# eurorack-passive-warp.net
KiCad netlist of a schematic drawn in EAGLE
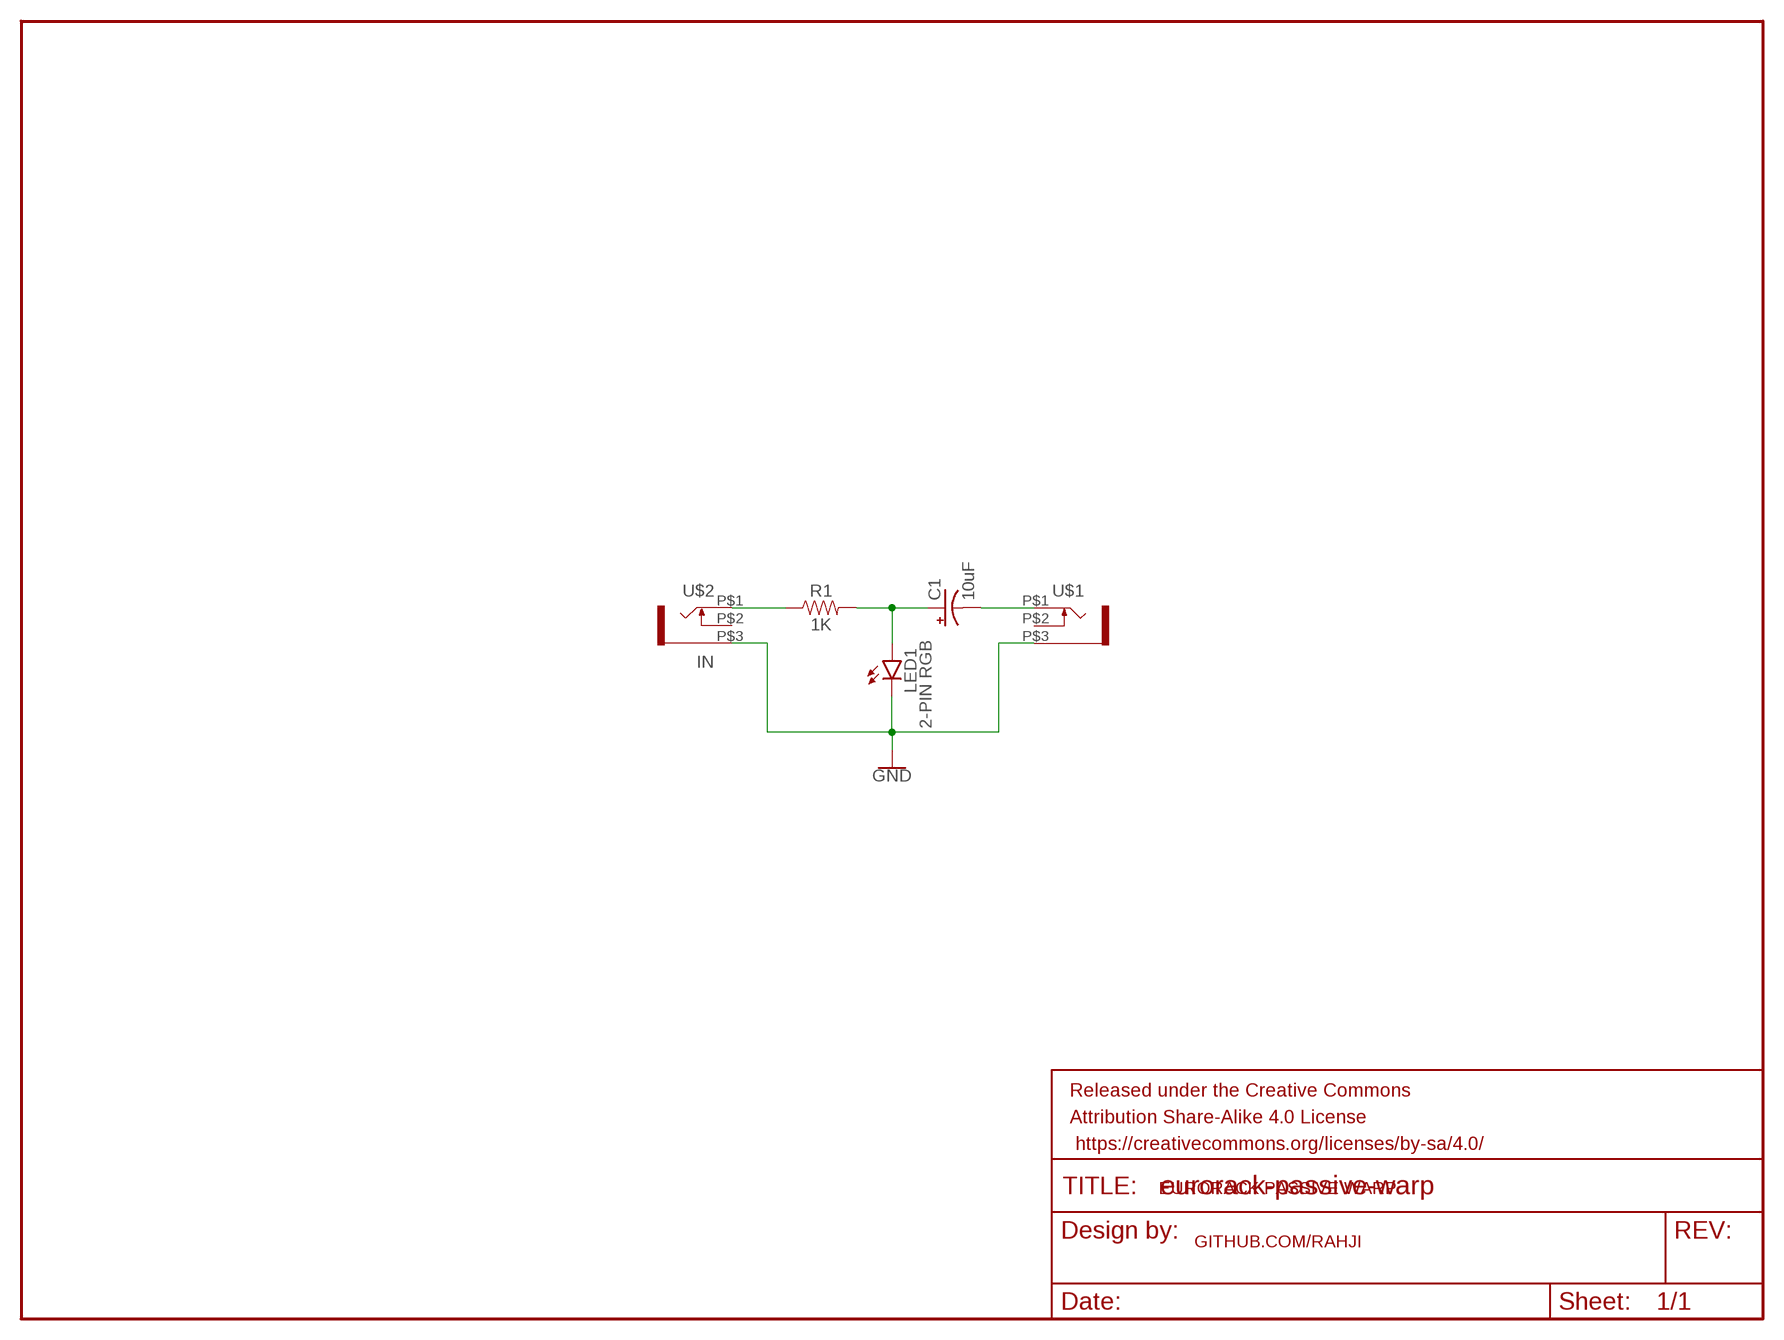
[diagram p0: schematic, sheet 1]

(export (version "E")
  (design (tool "Eeschema 10.0.6"))
  (components
    (comp (ref "C1")
      (value "10uF")
      (footprint "eagle-import:CPOL-RADIAL-2.5MM-5MM")
      (libsource (lib "eagle-import") (part "10UF-POLAR-RADIAL-2.5MM-25V-20%"))
    )
    (comp (ref "FRAME1")
      (value "FRAME-LETTERNO_PACKAGE")
      (footprint "eagle-import:DUMMY")
      (fields (field (name "DESIGNER") "Nobody"))
      (libsource (lib "eagle-import") (part "FRAME-LETTERNO_PACKAGE"))
    )
    (comp (ref "LED1")
      (value "2-PIN RGB")
      (footprint "eagle-import:LED5MM")
      (libsource (lib "eagle-import") (part "LED5MM"))
    )
    (comp (ref "R1")
      (value "1K")
      (footprint "eagle-import:AXIAL-0.3")
      (libsource (lib "eagle-import") (part "330OHM-HORIZ-1/10W-5%"))
    )
    (comp (ref "U$1")
      (value "OUT")
      (footprint "eagle-import:WQP-PJ301M-12_JACK")
      (libsource (lib "eagle-import") (part "WQP-PJ301M-12_JACK"))
    )
    (comp (ref "U$2")
      (value "IN")
      (footprint "eagle-import:WQP-PJ301M-12_JACK")
      (libsource (lib "eagle-import") (part "WQP-PJ301M-12_JACK"))
    )
  )
  (nets
    (net (code "1") (name "GND") (class "Default")
      (node (ref "LED1") (pin "K") (pinfunction "C_K") (pintype "passive"))
      (node (ref "U$1") (pin "P$3") (pinfunction "1_P$3") (pintype "passive"))
      (node (ref "U$2") (pin "P$3") (pinfunction "1_P$3") (pintype "passive"))
    )
    (net (code "2") (name "Net-(C1-+)") (class "Default")
      (node (ref "C1") (pin "1") (pinfunction "+_1") (pintype "passive"))
      (node (ref "LED1") (pin "A") (pinfunction "A_A") (pintype "passive"))
      (node (ref "R1") (pin "P$2") (pinfunction "2_P$2") (pintype "passive"))
    )
    (net (code "3") (name "Net-(C1--)") (class "Default")
      (node (ref "C1") (pin "2") (pinfunction "-_2") (pintype "passive"))
      (node (ref "U$1") (pin "P$1") (pinfunction "2_P$1") (pintype "passive"))
    )
    (net (code "4") (name "Net-(R1-1)") (class "Default")
      (node (ref "R1") (pin "P$1") (pinfunction "1_P$1") (pintype "passive"))
      (node (ref "U$2") (pin "P$1") (pinfunction "2_P$1") (pintype "passive"))
    )
    (net (code "5") (name "unconnected-(U$1-3-PadP$2)") (class "Default")
      (node (ref "U$1") (pin "P$2") (pinfunction "3_P$2") (pintype "passive"))
    )
    (net (code "6") (name "unconnected-(U$2-3-PadP$2)") (class "Default")
      (node (ref "U$2") (pin "P$2") (pinfunction "3_P$2") (pintype "passive"))
    )
  )
)
